# Arduino_Arcade_Stick.net
KiCad netlist of a schematic drawn in EAGLE
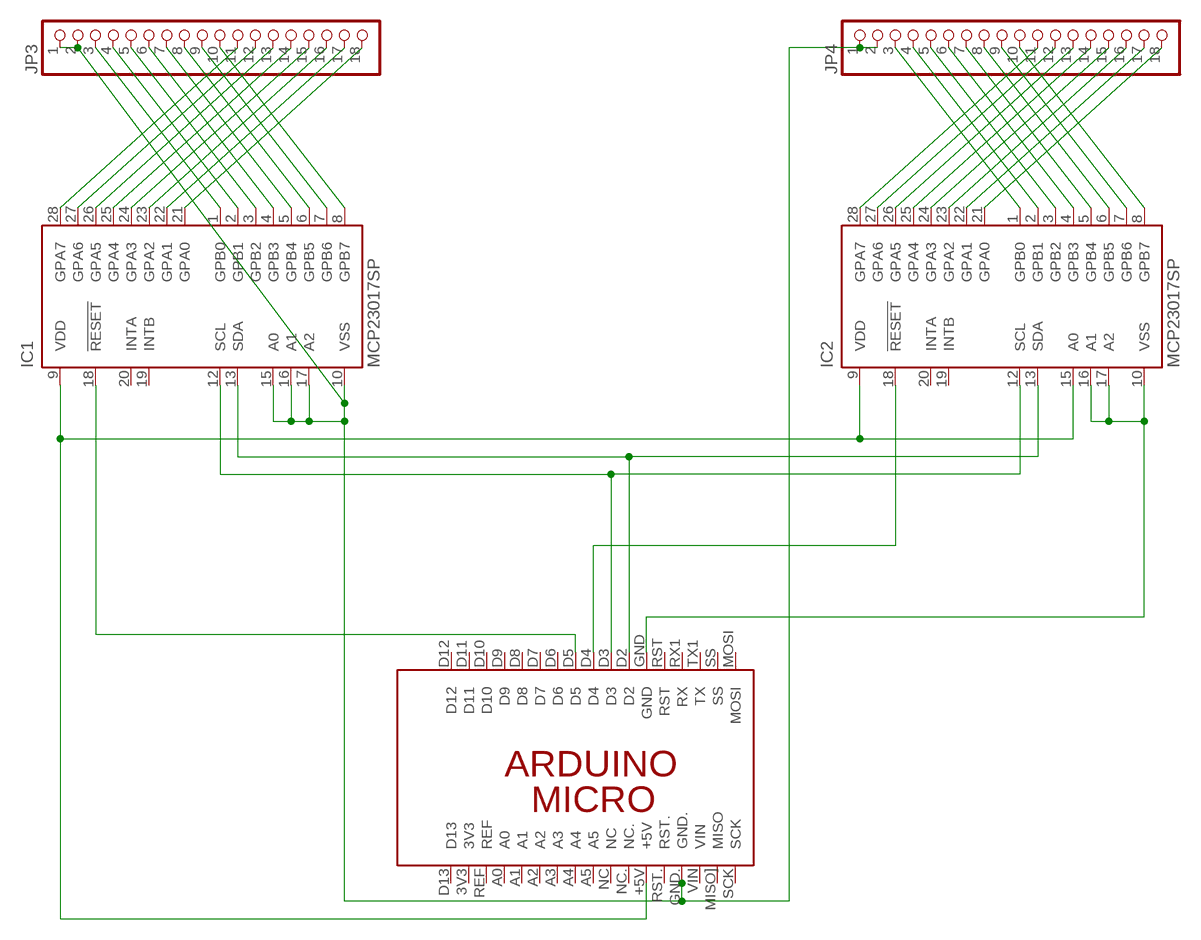
[diagram p0: schematic, sheet 1]

(export (version "E")
  (design (tool "Eeschema 10.0.6"))
  (components
    (comp (ref "IC1")
      (value "MCP23017SP")
      (footprint "eagle-import:DIL28-3")
      (libsource (lib "eagle-import") (part "MCP23017SP"))
    )
    (comp (ref "IC2")
      (value "MCP23017SP")
      (footprint "eagle-import:DIL28-3")
      (libsource (lib "eagle-import") (part "MCP23017SP"))
    )
    (comp (ref "JP3")
      (value "PINHD-1X18")
      (footprint "eagle-import:1X18")
      (libsource (lib "eagle-import") (part "PINHD-1X18"))
    )
    (comp (ref "JP4")
      (value "PINHD-1X18")
      (footprint "eagle-import:1X18")
      (libsource (lib "eagle-import") (part "PINHD-1X18"))
    )
    (comp (ref "PCB1")
      (value "ARDUINO_MICRO")
      (footprint "eagle-import:ARDUINO_MICRO")
      (libsource (lib "eagle-import") (part "ARDUINO_MICRO"))
    )
  )
  (nets
    (net (code "1") (name "/VSS") (class "Default")
      (node (ref "IC1") (pin "10") (pinfunction "VSS_10") (pintype "power_in"))
      (node (ref "IC1") (pin "15") (pinfunction "A0_15") (pintype "input"))
      (node (ref "IC1") (pin "16") (pinfunction "A1_16") (pintype "input"))
      (node (ref "IC1") (pin "17") (pinfunction "A2_17") (pintype "input"))
      (node (ref "IC2") (pin "10") (pinfunction "VSS_10") (pintype "power_in"))
      (node (ref "IC2") (pin "16") (pinfunction "A1_16") (pintype "input"))
      (node (ref "IC2") (pin "17") (pinfunction "A2_17") (pintype "input"))
      (node (ref "JP3") (pin "1") (pinfunction "1_1") (pintype "passive"))
      (node (ref "JP3") (pin "2") (pinfunction "2_2") (pintype "passive"))
      (node (ref "JP4") (pin "1") (pinfunction "1_1") (pintype "passive"))
      (node (ref "JP4") (pin "2") (pinfunction "2_2") (pintype "passive"))
      (node (ref "PCB1") (pin "GND") (pinfunction "GND_GND") (pintype "bidirectional"))
      (node (ref "PCB1") (pin "GND.") (pinfunction "GND._GND.") (pintype "bidirectional"))
    )
    (net (code "2") (name "Net-(IC1-GPA0)") (class "Default")
      (node (ref "IC1") (pin "21") (pinfunction "GPA0_21") (pintype "bidirectional"))
      (node (ref "JP3") (pin "18") (pinfunction "18_18") (pintype "passive"))
    )
    (net (code "3") (name "Net-(IC1-GPA1)") (class "Default")
      (node (ref "IC1") (pin "22") (pinfunction "GPA1_22") (pintype "bidirectional"))
      (node (ref "JP3") (pin "17") (pinfunction "17_17") (pintype "passive"))
    )
    (net (code "4") (name "Net-(IC1-GPA2)") (class "Default")
      (node (ref "IC1") (pin "23") (pinfunction "GPA2_23") (pintype "bidirectional"))
      (node (ref "JP3") (pin "16") (pinfunction "16_16") (pintype "passive"))
    )
    (net (code "5") (name "Net-(IC1-GPA3)") (class "Default")
      (node (ref "IC1") (pin "24") (pinfunction "GPA3_24") (pintype "bidirectional"))
      (node (ref "JP3") (pin "15") (pinfunction "15_15") (pintype "passive"))
    )
    (net (code "6") (name "Net-(IC1-GPA4)") (class "Default")
      (node (ref "IC1") (pin "25") (pinfunction "GPA4_25") (pintype "bidirectional"))
      (node (ref "JP3") (pin "14") (pinfunction "14_14") (pintype "passive"))
    )
    (net (code "7") (name "Net-(IC1-GPA5)") (class "Default")
      (node (ref "IC1") (pin "26") (pinfunction "GPA5_26") (pintype "bidirectional"))
      (node (ref "JP3") (pin "13") (pinfunction "13_13") (pintype "passive"))
    )
    (net (code "8") (name "Net-(IC1-GPA6)") (class "Default")
      (node (ref "IC1") (pin "27") (pinfunction "GPA6_27") (pintype "bidirectional"))
      (node (ref "JP3") (pin "12") (pinfunction "12_12") (pintype "passive"))
    )
    (net (code "9") (name "Net-(IC1-GPA7)") (class "Default")
      (node (ref "IC1") (pin "28") (pinfunction "GPA7_28") (pintype "bidirectional"))
      (node (ref "JP3") (pin "11") (pinfunction "11_11") (pintype "passive"))
    )
    (net (code "10") (name "Net-(IC1-GPB0)") (class "Default")
      (node (ref "IC1") (pin "1") (pinfunction "GPB0_1") (pintype "bidirectional"))
      (node (ref "JP3") (pin "3") (pinfunction "3_3") (pintype "passive"))
    )
    (net (code "11") (name "Net-(IC1-GPB1)") (class "Default")
      (node (ref "IC1") (pin "2") (pinfunction "GPB1_2") (pintype "bidirectional"))
      (node (ref "JP3") (pin "4") (pinfunction "4_4") (pintype "passive"))
    )
    (net (code "12") (name "Net-(IC1-GPB2)") (class "Default")
      (node (ref "IC1") (pin "3") (pinfunction "GPB2_3") (pintype "bidirectional"))
      (node (ref "JP3") (pin "5") (pinfunction "5_5") (pintype "passive"))
    )
    (net (code "13") (name "Net-(IC1-GPB3)") (class "Default")
      (node (ref "IC1") (pin "4") (pinfunction "GPB3_4") (pintype "bidirectional"))
      (node (ref "JP3") (pin "6") (pinfunction "6_6") (pintype "passive"))
    )
    (net (code "14") (name "Net-(IC1-GPB4)") (class "Default")
      (node (ref "IC1") (pin "5") (pinfunction "GPB4_5") (pintype "bidirectional"))
      (node (ref "JP3") (pin "7") (pinfunction "7_7") (pintype "passive"))
    )
    (net (code "15") (name "Net-(IC1-GPB5)") (class "Default")
      (node (ref "IC1") (pin "6") (pinfunction "GPB5_6") (pintype "bidirectional"))
      (node (ref "JP3") (pin "8") (pinfunction "8_8") (pintype "passive"))
    )
    (net (code "16") (name "Net-(IC1-GPB6)") (class "Default")
      (node (ref "IC1") (pin "7") (pinfunction "GPB6_7") (pintype "bidirectional"))
      (node (ref "JP3") (pin "9") (pinfunction "9_9") (pintype "passive"))
    )
    (net (code "17") (name "Net-(IC1-GPB7)") (class "Default")
      (node (ref "IC1") (pin "8") (pinfunction "GPB7_8") (pintype "bidirectional"))
      (node (ref "JP3") (pin "10") (pinfunction "10_10") (pintype "passive"))
    )
    (net (code "18") (name "Net-(IC1-SCL)") (class "Default")
      (node (ref "IC1") (pin "12") (pinfunction "SCL_12") (pintype "input"))
      (node (ref "IC2") (pin "12") (pinfunction "SCL_12") (pintype "input"))
      (node (ref "PCB1") (pin "D3") (pinfunction "D3_D3") (pintype "bidirectional"))
    )
    (net (code "19") (name "Net-(IC1-SDA)") (class "Default")
      (node (ref "IC1") (pin "13") (pinfunction "SDA_13") (pintype "bidirectional"))
      (node (ref "IC2") (pin "13") (pinfunction "SDA_13") (pintype "bidirectional"))
      (node (ref "PCB1") (pin "D2") (pinfunction "D2_D2") (pintype "bidirectional"))
    )
    (net (code "20") (name "Net-(IC1-VDD)") (class "Default")
      (node (ref "IC1") (pin "9") (pinfunction "VDD_9") (pintype "power_in"))
      (node (ref "IC2") (pin "15") (pinfunction "A0_15") (pintype "input"))
      (node (ref "IC2") (pin "9") (pinfunction "VDD_9") (pintype "power_in"))
      (node (ref "PCB1") (pin "+5V") (pinfunction "+5V_+5V") (pintype "bidirectional"))
    )
    (net (code "21") (name "Net-(IC1-~{RESET})") (class "Default")
      (node (ref "IC1") (pin "18") (pinfunction "~{RESET}_18") (pintype "input"))
      (node (ref "PCB1") (pin "D5") (pinfunction "D5_D5") (pintype "bidirectional"))
    )
    (net (code "22") (name "Net-(IC2-GPA0)") (class "Default")
      (node (ref "IC2") (pin "21") (pinfunction "GPA0_21") (pintype "bidirectional"))
      (node (ref "JP4") (pin "18") (pinfunction "18_18") (pintype "passive"))
    )
    (net (code "23") (name "Net-(IC2-GPA1)") (class "Default")
      (node (ref "IC2") (pin "22") (pinfunction "GPA1_22") (pintype "bidirectional"))
      (node (ref "JP4") (pin "17") (pinfunction "17_17") (pintype "passive"))
    )
    (net (code "24") (name "Net-(IC2-GPA2)") (class "Default")
      (node (ref "IC2") (pin "23") (pinfunction "GPA2_23") (pintype "bidirectional"))
      (node (ref "JP4") (pin "16") (pinfunction "16_16") (pintype "passive"))
    )
    (net (code "25") (name "Net-(IC2-GPA3)") (class "Default")
      (node (ref "IC2") (pin "24") (pinfunction "GPA3_24") (pintype "bidirectional"))
      (node (ref "JP4") (pin "15") (pinfunction "15_15") (pintype "passive"))
    )
    (net (code "26") (name "Net-(IC2-GPA4)") (class "Default")
      (node (ref "IC2") (pin "25") (pinfunction "GPA4_25") (pintype "bidirectional"))
      (node (ref "JP4") (pin "14") (pinfunction "14_14") (pintype "passive"))
    )
    (net (code "27") (name "Net-(IC2-GPA5)") (class "Default")
      (node (ref "IC2") (pin "26") (pinfunction "GPA5_26") (pintype "bidirectional"))
      (node (ref "JP4") (pin "13") (pinfunction "13_13") (pintype "passive"))
    )
    (net (code "28") (name "Net-(IC2-GPA6)") (class "Default")
      (node (ref "IC2") (pin "27") (pinfunction "GPA6_27") (pintype "bidirectional"))
      (node (ref "JP4") (pin "12") (pinfunction "12_12") (pintype "passive"))
    )
    (net (code "29") (name "Net-(IC2-GPA7)") (class "Default")
      (node (ref "IC2") (pin "28") (pinfunction "GPA7_28") (pintype "bidirectional"))
      (node (ref "JP4") (pin "11") (pinfunction "11_11") (pintype "passive"))
    )
    (net (code "30") (name "Net-(IC2-GPB0)") (class "Default")
      (node (ref "IC2") (pin "1") (pinfunction "GPB0_1") (pintype "bidirectional"))
      (node (ref "JP4") (pin "3") (pinfunction "3_3") (pintype "passive"))
    )
    (net (code "31") (name "Net-(IC2-GPB1)") (class "Default")
      (node (ref "IC2") (pin "2") (pinfunction "GPB1_2") (pintype "bidirectional"))
      (node (ref "JP4") (pin "4") (pinfunction "4_4") (pintype "passive"))
    )
    (net (code "32") (name "Net-(IC2-GPB2)") (class "Default")
      (node (ref "IC2") (pin "3") (pinfunction "GPB2_3") (pintype "bidirectional"))
      (node (ref "JP4") (pin "5") (pinfunction "5_5") (pintype "passive"))
    )
    (net (code "33") (name "Net-(IC2-GPB3)") (class "Default")
      (node (ref "IC2") (pin "4") (pinfunction "GPB3_4") (pintype "bidirectional"))
      (node (ref "JP4") (pin "6") (pinfunction "6_6") (pintype "passive"))
    )
    (net (code "34") (name "Net-(IC2-GPB4)") (class "Default")
      (node (ref "IC2") (pin "5") (pinfunction "GPB4_5") (pintype "bidirectional"))
      (node (ref "JP4") (pin "7") (pinfunction "7_7") (pintype "passive"))
    )
    (net (code "35") (name "Net-(IC2-GPB5)") (class "Default")
      (node (ref "IC2") (pin "6") (pinfunction "GPB5_6") (pintype "bidirectional"))
      (node (ref "JP4") (pin "8") (pinfunction "8_8") (pintype "passive"))
    )
    (net (code "36") (name "Net-(IC2-GPB6)") (class "Default")
      (node (ref "IC2") (pin "7") (pinfunction "GPB6_7") (pintype "bidirectional"))
      (node (ref "JP4") (pin "9") (pinfunction "9_9") (pintype "passive"))
    )
    (net (code "37") (name "Net-(IC2-GPB7)") (class "Default")
      (node (ref "IC2") (pin "8") (pinfunction "GPB7_8") (pintype "bidirectional"))
      (node (ref "JP4") (pin "10") (pinfunction "10_10") (pintype "passive"))
    )
    (net (code "38") (name "Net-(IC2-~{RESET})") (class "Default")
      (node (ref "IC2") (pin "18") (pinfunction "~{RESET}_18") (pintype "input"))
      (node (ref "PCB1") (pin "D4") (pinfunction "D4_D4") (pintype "bidirectional"))
    )
    (net (code "39") (name "unconnected-(IC1-INTA-Pad20)") (class "Default")
      (node (ref "IC1") (pin "20") (pinfunction "INTA_20") (pintype "output"))
    )
    (net (code "40") (name "unconnected-(IC1-INTB-Pad19)") (class "Default")
      (node (ref "IC1") (pin "19") (pinfunction "INTB_19") (pintype "output"))
    )
    (net (code "41") (name "unconnected-(IC2-INTA-Pad20)") (class "Default")
      (node (ref "IC2") (pin "20") (pinfunction "INTA_20") (pintype "output"))
    )
    (net (code "42") (name "unconnected-(IC2-INTB-Pad19)") (class "Default")
      (node (ref "IC2") (pin "19") (pinfunction "INTB_19") (pintype "output"))
    )
    (net (code "43") (name "unconnected-(PCB1-MISO-PadMISO])") (class "Default")
      (node (ref "PCB1") (pin "MISO]") (pinfunction "MISO_MISO]") (pintype "bidirectional"))
    )
    (net (code "44") (name "unconnected-(PCB1-Pad3V3)") (class "Default")
      (node (ref "PCB1") (pin "3V3") (pinfunction "3V3_3V3") (pintype "bidirectional"))
    )
    (net (code "45") (name "unconnected-(PCB1-PadA0)") (class "Default")
      (node (ref "PCB1") (pin "A0") (pinfunction "A0_A0") (pintype "bidirectional"))
    )
    (net (code "46") (name "unconnected-(PCB1-PadA1)") (class "Default")
      (node (ref "PCB1") (pin "A1") (pinfunction "A1_A1") (pintype "bidirectional"))
    )
    (net (code "47") (name "unconnected-(PCB1-PadA2)") (class "Default")
      (node (ref "PCB1") (pin "A2") (pinfunction "A2_A2") (pintype "bidirectional"))
    )
    (net (code "48") (name "unconnected-(PCB1-PadA3)") (class "Default")
      (node (ref "PCB1") (pin "A3") (pinfunction "A3_A3") (pintype "bidirectional"))
    )
    (net (code "49") (name "unconnected-(PCB1-PadA4)") (class "Default")
      (node (ref "PCB1") (pin "A4") (pinfunction "A4_A4") (pintype "bidirectional"))
    )
    (net (code "50") (name "unconnected-(PCB1-PadA5)") (class "Default")
      (node (ref "PCB1") (pin "A5") (pinfunction "A5_A5") (pintype "bidirectional"))
    )
    (net (code "51") (name "unconnected-(PCB1-PadD6)") (class "Default")
      (node (ref "PCB1") (pin "D6") (pinfunction "D6_D6") (pintype "bidirectional"))
    )
    (net (code "52") (name "unconnected-(PCB1-PadD7)") (class "Default")
      (node (ref "PCB1") (pin "D7") (pinfunction "D7_D7") (pintype "bidirectional"))
    )
    (net (code "53") (name "unconnected-(PCB1-PadD8)") (class "Default")
      (node (ref "PCB1") (pin "D8") (pinfunction "D8_D8") (pintype "bidirectional"))
    )
    (net (code "54") (name "unconnected-(PCB1-PadD9)") (class "Default")
      (node (ref "PCB1") (pin "D9") (pinfunction "D9_D9") (pintype "bidirectional"))
    )
    (net (code "55") (name "unconnected-(PCB1-PadD10)") (class "Default")
      (node (ref "PCB1") (pin "D10") (pinfunction "D10_D10") (pintype "bidirectional"))
    )
    (net (code "56") (name "unconnected-(PCB1-PadD11)") (class "Default")
      (node (ref "PCB1") (pin "D11") (pinfunction "D11_D11") (pintype "bidirectional"))
    )
    (net (code "57") (name "unconnected-(PCB1-PadD12)") (class "Default")
      (node (ref "PCB1") (pin "D12") (pinfunction "D12_D12") (pintype "bidirectional"))
    )
    (net (code "58") (name "unconnected-(PCB1-PadD13)") (class "Default")
      (node (ref "PCB1") (pin "D13") (pinfunction "D13_D13") (pintype "bidirectional"))
    )
    (net (code "59") (name "unconnected-(PCB1-PadMOSI)") (class "Default")
      (node (ref "PCB1") (pin "MOSI") (pinfunction "MOSI_MOSI") (pintype "bidirectional"))
    )
    (net (code "60") (name "unconnected-(PCB1-PadNC)") (class "Default")
      (node (ref "PCB1") (pin "NC") (pinfunction "NC_NC") (pintype "bidirectional"))
    )
    (net (code "61") (name "unconnected-(PCB1-PadNC.)") (class "Default")
      (node (ref "PCB1") (pin "NC.") (pinfunction "NC._NC.") (pintype "bidirectional"))
    )
    (net (code "62") (name "unconnected-(PCB1-PadREF)") (class "Default")
      (node (ref "PCB1") (pin "REF") (pinfunction "REF_REF") (pintype "bidirectional"))
    )
    (net (code "63") (name "unconnected-(PCB1-PadRST)") (class "Default")
      (node (ref "PCB1") (pin "RST") (pinfunction "RST_RST") (pintype "bidirectional"))
    )
    (net (code "64") (name "unconnected-(PCB1-PadRST.)") (class "Default")
      (node (ref "PCB1") (pin "RST.") (pinfunction "RST._RST.") (pintype "bidirectional"))
    )
    (net (code "65") (name "unconnected-(PCB1-PadSCK)") (class "Default")
      (node (ref "PCB1") (pin "SCK") (pinfunction "SCK_SCK") (pintype "bidirectional"))
    )
    (net (code "66") (name "unconnected-(PCB1-PadSS)") (class "Default")
      (node (ref "PCB1") (pin "SS") (pinfunction "SS_SS") (pintype "bidirectional"))
    )
    (net (code "67") (name "unconnected-(PCB1-PadVIN)") (class "Default")
      (node (ref "PCB1") (pin "VIN") (pinfunction "VIN_VIN") (pintype "bidirectional"))
    )
    (net (code "68") (name "unconnected-(PCB1-RX-PadRX1)") (class "Default")
      (node (ref "PCB1") (pin "RX1") (pinfunction "RX_RX1") (pintype "bidirectional"))
    )
    (net (code "69") (name "unconnected-(PCB1-TX-PadTX1)") (class "Default")
      (node (ref "PCB1") (pin "TX1") (pinfunction "TX_TX1") (pintype "bidirectional"))
    )
  )
)
